# Servo_interface.net
KiCad netlist of a schematic drawn in Altium Designer
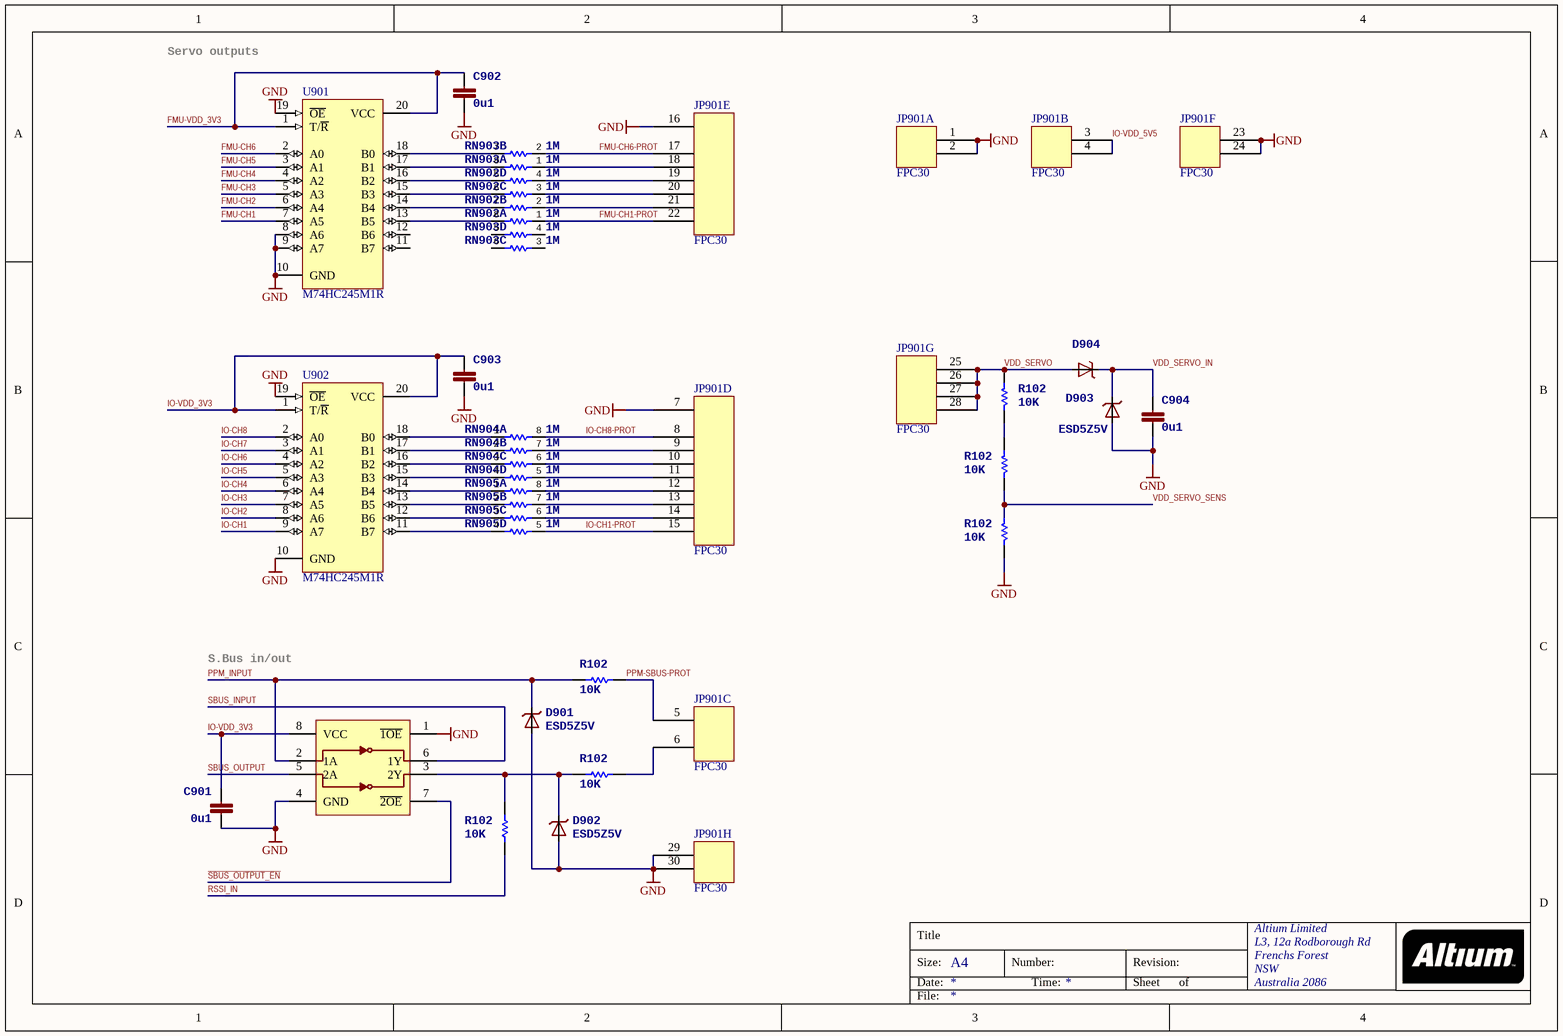
[diagram p0: Servo interface.SchDoc]

(export (version "E")
  (design (tool "Eeschema 10.0.6"))
  (components
    (comp (ref "C901")
      (value "0u1")
      (footprint "0603-CAP")
      (description "<b>Capacitor</b>\nStandard 0603 ceramic capacitor, and 0.1\" leaded capacitor.")
      (fields
        (field (name "PARTNO") "CC0402ZRY5V7BB104")
        (field (name ">NAME") "C901")
        (field (name ">VALUE") "0u1")
      )
      (libsource (lib "") (part "CAP0402_1"))
    )
    (comp (ref "C902")
      (value "0u1")
      (footprint "0603-CAP")
      (description "<b>Capacitor</b>\nStandard 0603 ceramic capacitor, and 0.1\" leaded capacitor.")
      (fields
        (field (name "PARTNO") "CC0402ZRY5V7BB104")
        (field (name ">NAME") "C902")
        (field (name ">VALUE") "0u1")
      )
      (libsource (lib "pixhawk2") (part "CAP0402"))
    )
    (comp (ref "C903")
      (value "0u1")
      (footprint "0603-CAP")
      (description "<b>Capacitor</b>\nStandard 0603 ceramic capacitor, and 0.1\" leaded capacitor.")
      (fields
        (field (name "PARTNO") "CC0402ZRY5V7BB104")
        (field (name ">NAME") "C903")
        (field (name ">VALUE") "0u1")
      )
      (libsource (lib "pixhawk2") (part "CAP0402"))
    )
    (comp (ref "C904")
      (value "0u1")
      (footprint "0603-CAP")
      (description "<b>Capacitor</b>\nStandard 0603 ceramic capacitor, and 0.1\" leaded capacitor.")
      (fields
        (field (name "PARTNO") "CC0402ZRY5V7BB104")
        (field (name ">NAME") "C904")
        (field (name ">VALUE") "0u1")
      )
      (libsource (lib "pixhawk2") (part "CAP0402"))
    )
    (comp (ref "D901") (value "ESD5Z5V") (footprint "SOD523") (libsource (lib "pixhawk2") (part "DIODE-TVS")))
    (comp (ref "D902") (value "ESD5Z5V") (footprint "SOD523") (libsource (lib "pixhawk2") (part "DIODE-TVS")))
    (comp (ref "D903") (value "ESD5Z5V") (footprint "SOD523") (libsource (lib "pixhawk2") (part "DIODE-TVS")))
    (comp (ref "D904")
      (value "SS14 SOD323")
      (footprint "SOD323")
      (description "Schottky barrier diode in DO214AC, e.g. Fairchild SS14.")
      (libsource (lib "pixhawk2") (part "DIODE-SCHOTTKY_MSMP"))
    )
    (comp (ref "JP901") (value "FPC30") (footprint "FPC-0.5-30下接带锁") (libsource (lib "") (part "FPC30_1")))
    (comp (ref "R901")
      (value "10K")
      (footprint "0603-RES")
      (fields
        (field (name "PARTNO") "RC0402FR-0710KL")
        (field (name ">NAME") "R102")
        (field (name ">VALUE") "10K")
      )
      (libsource (lib "PX4") (part "RESISTOR0402-RES"))
    )
    (comp (ref "R909")
      (value "10K")
      (footprint "0603-RES")
      (fields
        (field (name "PARTNO") "RC0402FR-0710KL")
        (field (name ">NAME") "R102")
        (field (name ">VALUE") "10K")
      )
      (libsource (lib "PX4") (part "RESISTOR0402-RES"))
    )
    (comp (ref "R910")
      (value "10K")
      (footprint "0603-RES")
      (fields
        (field (name "PARTNO") "RC0402FR-0710KL")
        (field (name ">NAME") "R102")
        (field (name ">VALUE") "10K")
      )
      (libsource (lib "PX4") (part "RESISTOR0402-RES"))
    )
    (comp (ref "R918")
      (value "10K")
      (footprint "0603-RES")
      (fields
        (field (name "PARTNO") "RC0402FR-0710KL")
        (field (name ">NAME") "R102")
        (field (name ">VALUE") "10K")
      )
      (libsource (lib "PX4") (part "RESISTOR0402-RES"))
    )
    (comp (ref "R919")
      (value "10K")
      (footprint "0603-RES")
      (fields
        (field (name "PARTNO") "RC0402FR-0710KL")
        (field (name ">NAME") "R102")
        (field (name ">VALUE") "10K")
      )
      (libsource (lib "PX4") (part "RESISTOR0402-RES"))
    )
    (comp (ref "R922")
      (value "10K")
      (footprint "0603-RES")
      (fields
        (field (name "PARTNO") "RC0402FR-0710KL")
        (field (name ">NAME") "R102")
        (field (name ">VALUE") "10K")
      )
      (libsource (lib "PX4") (part "RESISTOR0402-RES"))
    )
    (comp (ref "RN902")
      (value "1M")
      (footprint "EXB28V")
      (description "<b>Array Chip Resistor</b><p>\nSource: RS Component / Phycomp")
      (fields (field (name "PARTNO") "EXB-28V105JX"))
      (libsource (lib "PX4") (part "4R-NEXB28V"))
    )
    (comp (ref "RN903")
      (value "1M")
      (footprint "EXB28V")
      (description "<b>Array Chip Resistor</b><p>\nSource: RS Component / Phycomp")
      (fields (field (name "PARTNO") "EXB-28V105JX"))
      (libsource (lib "PX4") (part "4R-NEXB28V"))
    )
    (comp (ref "RN904")
      (value "1M")
      (footprint "EXB28V")
      (description "<b>Array Chip Resistor</b><p>\nSource: RS Component / Phycomp")
      (fields (field (name "PARTNO") "EXB-28V105JX"))
      (libsource (lib "PX4") (part "4R-NEXB28V"))
    )
    (comp (ref "RN905")
      (value "1M")
      (footprint "EXB28V")
      (description "<b>Array Chip Resistor</b><p>\nSource: RS Component / Phycomp")
      (fields (field (name "PARTNO") "EXB-28V105JX"))
      (libsource (lib "PX4") (part "4R-NEXB28V"))
    )
    (comp (ref "U901")
      (value "M74HC245M1R")
      (footprint "TSSOP20")
      (description "Octal Bus Transceiver 3-State Non-Inverting")
      (fields (field (name "PUBLISHER") "Altium Limited"))
      (libsource (lib "ST Interface Line Transceiver") (part "M74HC245M1R"))
    )
    (comp (ref "U902")
      (value "M74HC245M1R")
      (footprint "TSSOP20")
      (description "Octal Bus Transceiver 3-State Non-Inverting")
      (fields (field (name "PUBLISHER") "Altium Limited"))
      (libsource (lib "ST Interface Line Transceiver") (part "M74HC245M1R"))
    )
    (comp (ref "U903")
      (value "74LVC2G240")
      (footprint "TSSOP8_SOT505-2")
      (fields (field (name "PARTNO") "74LVC2G240DP,125"))
      (libsource (lib "PX4") (part "74LVC2G240-TSSOP-8"))
    )
  )
  (nets
    (net (code "1") (name "/FMU-CH1") (class "Default")
      (node (ref "U901") (pin "7") (pinfunction "A5_7") (pintype "bidirectional"))
    )
    (net (code "2") (name "/FMU-CH1-PROT") (class "Default")
      (node (ref "JP901") (pin "22") (pintype "passive"))
      (node (ref "RN902") (pin "1") (pinfunction "1_1") (pintype "passive"))
    )
    (net (code "3") (name "/FMU-CH2") (class "Default")
      (node (ref "U901") (pin "6") (pinfunction "A4_6") (pintype "bidirectional"))
    )
    (net (code "4") (name "/FMU-CH3") (class "Default")
      (node (ref "U901") (pin "5") (pinfunction "A3_5") (pintype "bidirectional"))
    )
    (net (code "5") (name "/FMU-CH4") (class "Default")
      (node (ref "U901") (pin "4") (pinfunction "A2_4") (pintype "bidirectional"))
    )
    (net (code "6") (name "/FMU-CH5") (class "Default")
      (node (ref "U901") (pin "3") (pinfunction "A1_3") (pintype "bidirectional"))
    )
    (net (code "7") (name "/FMU-CH6") (class "Default")
      (node (ref "U901") (pin "2") (pinfunction "A0_2") (pintype "bidirectional"))
    )
    (net (code "8") (name "/FMU-CH6-PROT") (class "Default")
      (node (ref "JP901") (pin "17") (pintype "passive"))
      (node (ref "RN903") (pin "2") (pinfunction "1_2") (pintype "passive"))
    )
    (net (code "9") (name "/FMU-VDD_3V3") (class "Default")
      (node (ref "C902") (pin "P$1") (pinfunction "1_P$1") (pintype "passive"))
      (node (ref "U901") (pin "1") (pinfunction "T/~{R}_1") (pintype "input"))
      (node (ref "U901") (pin "20") (pinfunction "VCC_20") (pintype "power_in"))
    )
    (net (code "10") (name "/IO-CH1") (class "Default")
      (node (ref "U902") (pin "9") (pinfunction "A7_9") (pintype "bidirectional"))
    )
    (net (code "11") (name "/IO-CH1-PROT") (class "Default")
      (node (ref "JP901") (pin "15") (pintype "passive"))
      (node (ref "RN905") (pin "5") (pinfunction "2_5") (pintype "passive"))
    )
    (net (code "12") (name "/IO-CH2") (class "Default")
      (node (ref "U902") (pin "8") (pinfunction "A6_8") (pintype "bidirectional"))
    )
    (net (code "13") (name "/IO-CH3") (class "Default")
      (node (ref "U902") (pin "7") (pinfunction "A5_7") (pintype "bidirectional"))
    )
    (net (code "14") (name "/IO-CH4") (class "Default")
      (node (ref "U902") (pin "6") (pinfunction "A4_6") (pintype "bidirectional"))
    )
    (net (code "15") (name "/IO-CH5") (class "Default")
      (node (ref "U902") (pin "5") (pinfunction "A3_5") (pintype "bidirectional"))
    )
    (net (code "16") (name "/IO-CH6") (class "Default")
      (node (ref "U902") (pin "4") (pinfunction "A2_4") (pintype "bidirectional"))
    )
    (net (code "17") (name "/IO-CH7") (class "Default")
      (node (ref "U902") (pin "3") (pinfunction "A1_3") (pintype "bidirectional"))
    )
    (net (code "18") (name "/IO-CH8") (class "Default")
      (node (ref "U902") (pin "2") (pinfunction "A0_2") (pintype "bidirectional"))
    )
    (net (code "19") (name "/IO-CH8-PROT") (class "Default")
      (node (ref "JP901") (pin "8") (pintype "passive"))
      (node (ref "RN904") (pin "8") (pinfunction "2_8") (pintype "passive"))
    )
    (net (code "20") (name "/IO-VDD_3V3") (class "Default")
      (node (ref "C901") (pin "P$1") (pinfunction "1_P$1") (pintype "passive"))
      (node (ref "C903") (pin "P$1") (pinfunction "1_P$1") (pintype "passive"))
      (node (ref "U902") (pin "1") (pinfunction "T/~{R}_1") (pintype "input"))
      (node (ref "U902") (pin "20") (pinfunction "VCC_20") (pintype "power_in"))
      (node (ref "U903") (pin "8") (pinfunction "VCC_8") (pintype "open_emitter"))
    )
    (net (code "21") (name "/IO-VDD_5V5") (class "Default")
      (node (ref "JP901") (pin "3") (pintype "passive"))
      (node (ref "JP901") (pin "4") (pintype "passive"))
    )
    (net (code "22") (name "/PPM-SBUS-PROT") (class "Default")
      (node (ref "JP901") (pin "5") (pintype "passive"))
      (node (ref "R909") (pin "P$2") (pinfunction "2_P$2") (pintype "passive"))
    )
    (net (code "23") (name "/PPM_INPUT") (class "Default")
      (node (ref "D901") (pin "C") (pinfunction "C_C") (pintype "passive"))
      (node (ref "R909") (pin "P$1") (pinfunction "1_P$1") (pintype "passive"))
      (node (ref "U903") (pin "2") (pinfunction "1A_2") (pintype "passive"))
    )
    (net (code "24") (name "/RSSI_IN") (class "Default")
      (node (ref "R901") (pin "P$1") (pinfunction "1_P$1") (pintype "passive"))
    )
    (net (code "25") (name "/SBUS_INPUT") (class "Default")
      (node (ref "U903") (pin "6") (pinfunction "1Y_6") (pintype "passive"))
    )
    (net (code "26") (name "/SBUS_OUTPUT") (class "Default")
      (node (ref "U903") (pin "5") (pinfunction "2A_5") (pintype "passive"))
    )
    (net (code "27") (name "/VDD_SERVO") (class "Default")
      (node (ref "D904") (pin "A") (pinfunction "A_A") (pintype "passive"))
      (node (ref "JP901") (pin "25") (pintype "passive"))
      (node (ref "JP901") (pin "26") (pintype "passive"))
      (node (ref "JP901") (pin "27") (pintype "passive"))
      (node (ref "JP901") (pin "28") (pintype "passive"))
      (node (ref "R922") (pin "P$2") (pinfunction "2_P$2") (pintype "passive"))
    )
    (net (code "28") (name "/VDD_SERVO_IN") (class "Default")
      (node (ref "C904") (pin "P$1") (pinfunction "1_P$1") (pintype "passive"))
      (node (ref "D903") (pin "C") (pinfunction "C_C") (pintype "passive"))
      (node (ref "D904") (pin "C") (pinfunction "C_C") (pintype "passive"))
    )
    (net (code "29") (name "/VDD_SERVO_SENS") (class "Default")
      (node (ref "R918") (pin "P$1") (pinfunction "1_P$1") (pintype "passive"))
      (node (ref "R919") (pin "P$2") (pinfunction "2_P$2") (pintype "passive"))
    )
    (net (code "30") (name "/~{SBUS_OUTPUT_EN}") (class "Default")
      (node (ref "U903") (pin "7") (pinfunction "~{2OE}_7") (pintype "passive"))
    )
    (net (code "31") (name "GND") (class "Default")
      (node (ref "C901") (pin "P$2") (pinfunction "2_P$2") (pintype "passive"))
      (node (ref "C902") (pin "P$2") (pinfunction "2_P$2") (pintype "passive"))
      (node (ref "C903") (pin "P$2") (pinfunction "2_P$2") (pintype "passive"))
      (node (ref "C904") (pin "P$2") (pinfunction "2_P$2") (pintype "passive"))
      (node (ref "D901") (pin "A") (pinfunction "A_A") (pintype "passive"))
      (node (ref "D902") (pin "A") (pinfunction "A_A") (pintype "passive"))
      (node (ref "D903") (pin "A") (pinfunction "A_A") (pintype "passive"))
      (node (ref "JP901") (pin "1") (pintype "passive"))
      (node (ref "JP901") (pin "16") (pintype "passive"))
      (node (ref "JP901") (pin "2") (pintype "passive"))
      (node (ref "JP901") (pin "23") (pintype "passive"))
      (node (ref "JP901") (pin "24") (pintype "passive"))
      (node (ref "JP901") (pin "29") (pintype "passive"))
      (node (ref "JP901") (pin "30") (pintype "passive"))
      (node (ref "JP901") (pin "7") (pintype "passive"))
      (node (ref "R919") (pin "P$1") (pinfunction "1_P$1") (pintype "passive"))
      (node (ref "U901") (pin "10") (pinfunction "GND_10") (pintype "power_in"))
      (node (ref "U901") (pin "19") (pinfunction "~{OE}_19") (pintype "input"))
      (node (ref "U901") (pin "8") (pinfunction "A6_8") (pintype "bidirectional"))
      (node (ref "U901") (pin "9") (pinfunction "A7_9") (pintype "bidirectional"))
      (node (ref "U902") (pin "10") (pinfunction "GND_10") (pintype "power_in"))
      (node (ref "U902") (pin "19") (pinfunction "~{OE}_19") (pintype "input"))
      (node (ref "U903") (pin "1") (pinfunction "~{1OE}_1") (pintype "passive"))
      (node (ref "U903") (pin "4") (pinfunction "GND_4") (pintype "open_emitter"))
    )
    (net (code "32") (name "Net-(JP901-Pad18)") (class "Default")
      (node (ref "JP901") (pin "18") (pintype "passive"))
      (node (ref "RN903") (pin "1") (pinfunction "1_1") (pintype "passive"))
    )
    (net (code "33") (name "Net-(R901-2)") (class "Default")
      (node (ref "D902") (pin "C") (pinfunction "C_C") (pintype "passive"))
      (node (ref "R901") (pin "P$2") (pinfunction "2_P$2") (pintype "passive"))
      (node (ref "R910") (pin "P$1") (pinfunction "1_P$1") (pintype "passive"))
      (node (ref "U903") (pin "3") (pinfunction "2Y_3") (pintype "passive"))
    )
    (net (code "34") (name "Net-(R910-2)") (class "Default")
      (node (ref "JP901") (pin "6") (pintype "passive"))
      (node (ref "R910") (pin "P$2") (pinfunction "2_P$2") (pintype "passive"))
    )
    (net (code "35") (name "Net-(R918-2)") (class "Default")
      (node (ref "R918") (pin "P$2") (pinfunction "2_P$2") (pintype "passive"))
      (node (ref "R922") (pin "P$1") (pinfunction "1_P$1") (pintype "passive"))
    )
    (net (code "36") (name "Net-(RN902A-2)") (class "Default")
      (node (ref "RN902") (pin "8") (pinfunction "2_8") (pintype "passive"))
      (node (ref "U901") (pin "13") (pinfunction "B5_13") (pintype "bidirectional"))
    )
    (net (code "37") (name "Net-(RN902B-1)") (class "Default")
      (node (ref "JP901") (pin "21") (pintype "passive"))
      (node (ref "RN902") (pin "2") (pinfunction "1_2") (pintype "passive"))
    )
    (net (code "38") (name "Net-(RN902B-2)") (class "Default")
      (node (ref "RN902") (pin "7") (pinfunction "2_7") (pintype "passive"))
      (node (ref "U901") (pin "14") (pinfunction "B4_14") (pintype "bidirectional"))
    )
    (net (code "39") (name "Net-(RN902C-1)") (class "Default")
      (node (ref "JP901") (pin "20") (pintype "passive"))
      (node (ref "RN902") (pin "3") (pinfunction "1_3") (pintype "passive"))
    )
    (net (code "40") (name "Net-(RN902C-2)") (class "Default")
      (node (ref "RN902") (pin "6") (pinfunction "2_6") (pintype "passive"))
      (node (ref "U901") (pin "15") (pinfunction "B3_15") (pintype "bidirectional"))
    )
    (net (code "41") (name "Net-(RN902D-1)") (class "Default")
      (node (ref "JP901") (pin "19") (pintype "passive"))
      (node (ref "RN902") (pin "4") (pinfunction "1_4") (pintype "passive"))
    )
    (net (code "42") (name "Net-(RN902D-2)") (class "Default")
      (node (ref "RN902") (pin "5") (pinfunction "2_5") (pintype "passive"))
      (node (ref "U901") (pin "16") (pinfunction "B2_16") (pintype "bidirectional"))
    )
    (net (code "43") (name "Net-(RN903A-2)") (class "Default")
      (node (ref "RN903") (pin "8") (pinfunction "2_8") (pintype "passive"))
      (node (ref "U901") (pin "17") (pinfunction "B1_17") (pintype "bidirectional"))
    )
    (net (code "44") (name "Net-(RN903B-2)") (class "Default")
      (node (ref "RN903") (pin "7") (pinfunction "2_7") (pintype "passive"))
      (node (ref "U901") (pin "18") (pinfunction "B0_18") (pintype "bidirectional"))
    )
    (net (code "45") (name "Net-(RN904B-1)") (class "Default")
      (node (ref "RN904") (pin "2") (pinfunction "1_2") (pintype "passive"))
      (node (ref "U902") (pin "17") (pinfunction "B1_17") (pintype "bidirectional"))
    )
    (net (code "46") (name "Net-(RN904B-2)") (class "Default")
      (node (ref "JP901") (pin "9") (pintype "passive"))
      (node (ref "RN904") (pin "7") (pinfunction "2_7") (pintype "passive"))
    )
    (net (code "47") (name "Net-(RN904C-1)") (class "Default")
      (node (ref "RN904") (pin "3") (pinfunction "1_3") (pintype "passive"))
      (node (ref "U902") (pin "16") (pinfunction "B2_16") (pintype "bidirectional"))
    )
    (net (code "48") (name "Net-(RN904C-2)") (class "Default")
      (node (ref "JP901") (pin "10") (pintype "passive"))
      (node (ref "RN904") (pin "6") (pinfunction "2_6") (pintype "passive"))
    )
    (net (code "49") (name "Net-(RN904D-1)") (class "Default")
      (node (ref "RN904") (pin "4") (pinfunction "1_4") (pintype "passive"))
      (node (ref "U902") (pin "15") (pinfunction "B3_15") (pintype "bidirectional"))
    )
    (net (code "50") (name "Net-(RN904D-2)") (class "Default")
      (node (ref "JP901") (pin "11") (pintype "passive"))
      (node (ref "RN904") (pin "5") (pinfunction "2_5") (pintype "passive"))
    )
    (net (code "51") (name "Net-(RN905A-2)") (class "Default")
      (node (ref "JP901") (pin "12") (pintype "passive"))
      (node (ref "RN905") (pin "8") (pinfunction "2_8") (pintype "passive"))
    )
    (net (code "52") (name "Net-(RN905B-1)") (class "Default")
      (node (ref "RN905") (pin "2") (pinfunction "1_2") (pintype "passive"))
      (node (ref "U902") (pin "13") (pinfunction "B5_13") (pintype "bidirectional"))
    )
    (net (code "53") (name "Net-(RN905B-2)") (class "Default")
      (node (ref "JP901") (pin "13") (pintype "passive"))
      (node (ref "RN905") (pin "7") (pinfunction "2_7") (pintype "passive"))
    )
    (net (code "54") (name "Net-(RN905C-1)") (class "Default")
      (node (ref "RN905") (pin "3") (pinfunction "1_3") (pintype "passive"))
      (node (ref "U902") (pin "12") (pinfunction "B6_12") (pintype "bidirectional"))
    )
    (net (code "55") (name "Net-(RN905C-2)") (class "Default")
      (node (ref "JP901") (pin "14") (pintype "passive"))
      (node (ref "RN905") (pin "6") (pinfunction "2_6") (pintype "passive"))
    )
    (net (code "56") (name "Net-(RN905D-1)") (class "Default")
      (node (ref "RN905") (pin "4") (pinfunction "1_4") (pintype "passive"))
      (node (ref "U902") (pin "11") (pinfunction "B7_11") (pintype "bidirectional"))
    )
    (net (code "57") (name "Net-(U902-B0)") (class "Default")
      (node (ref "RN904") (pin "1") (pinfunction "1_1") (pintype "passive"))
      (node (ref "U902") (pin "18") (pinfunction "B0_18") (pintype "bidirectional"))
    )
    (net (code "58") (name "Net-(U902-B4)") (class "Default")
      (node (ref "RN905") (pin "1") (pinfunction "1_1") (pintype "passive"))
      (node (ref "U902") (pin "14") (pinfunction "B4_14") (pintype "bidirectional"))
    )
    (net (code "59") (name "unconnected-(RN903C-1-Pad3)") (class "Default")
      (node (ref "RN903") (pin "3") (pinfunction "1_3") (pintype "passive"))
    )
    (net (code "60") (name "unconnected-(RN903C-2-Pad6)") (class "Default")
      (node (ref "RN903") (pin "6") (pinfunction "2_6") (pintype "passive"))
    )
    (net (code "61") (name "unconnected-(RN903D-1-Pad4)") (class "Default")
      (node (ref "RN903") (pin "4") (pinfunction "1_4") (pintype "passive"))
    )
    (net (code "62") (name "unconnected-(RN903D-2-Pad5)") (class "Default")
      (node (ref "RN903") (pin "5") (pinfunction "2_5") (pintype "passive"))
    )
    (net (code "63") (name "unconnected-(U901-B6-Pad12)") (class "Default")
      (node (ref "U901") (pin "12") (pinfunction "B6_12") (pintype "bidirectional"))
    )
    (net (code "64") (name "unconnected-(U901-B7-Pad11)") (class "Default")
      (node (ref "U901") (pin "11") (pinfunction "B7_11") (pintype "bidirectional"))
    )
  )
)
